# ESP32_breakout.net
KiCad netlist of a schematic drawn in Altium Designer
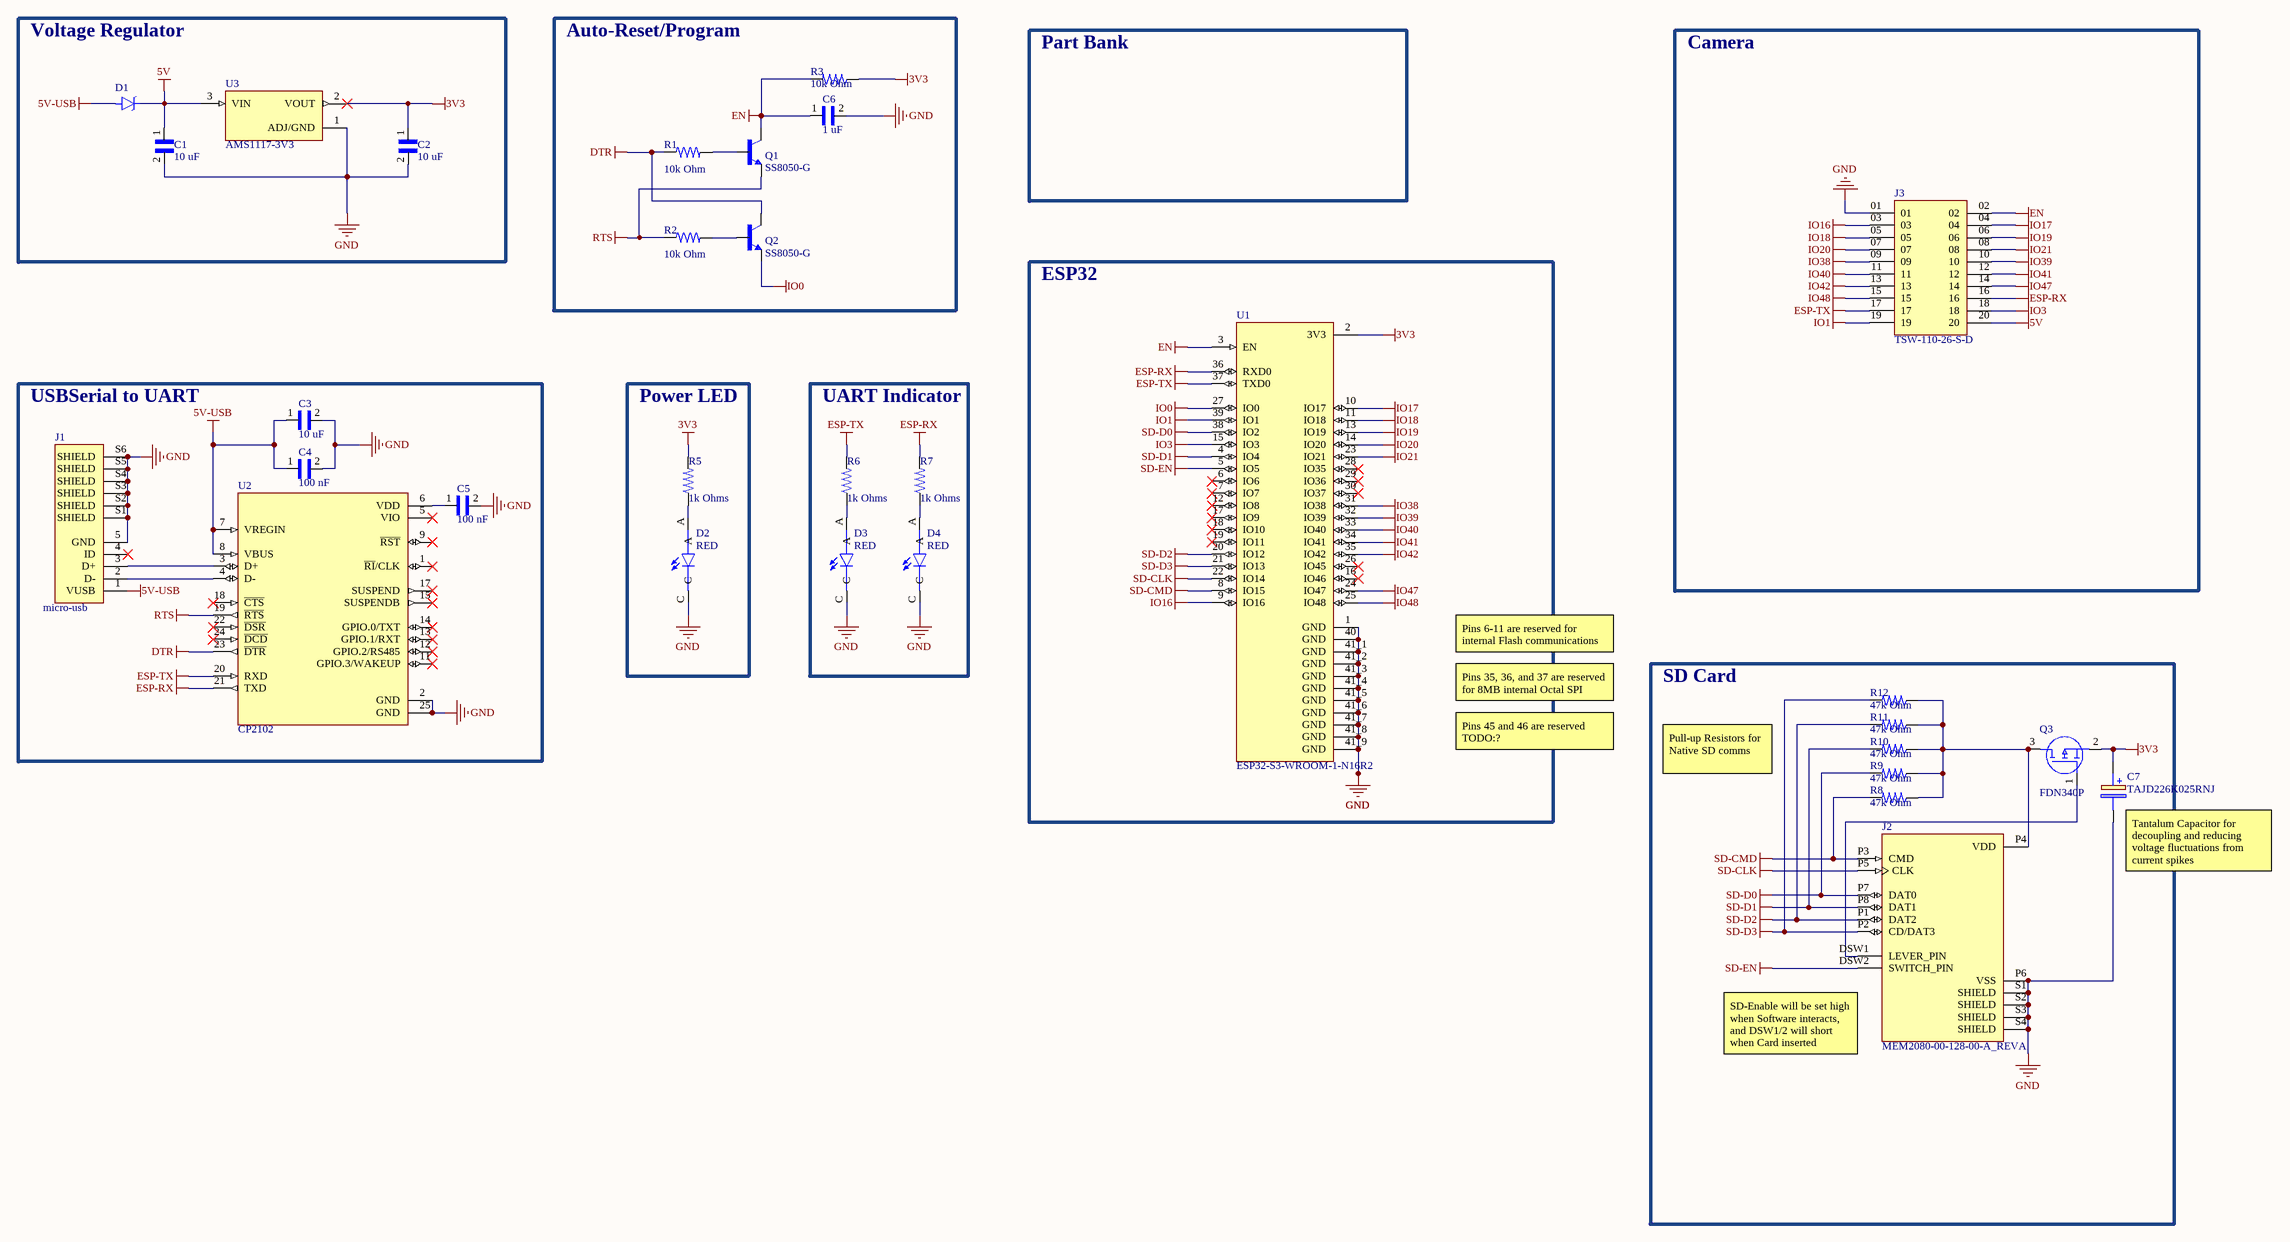
[diagram p0: ESP32_breakout.SchDoc]

(export (version "E")
  (design (tool "Eeschema 10.0.6"))
  (components
    (comp (ref "C1")
      (value "10 uF")
      (footprint "CAPC1608X90")
      (description "COMMERCIAL CHIP STD JAPAN BULK - FN TAPE/REEL, 7 INCH PAPER TAPE")
      (fields (field (name "MP") "LD03ZD475MAB2A"))
      (libsource (lib "") (part "LD03ZD475MAB2A_1"))
    )
    (comp (ref "C2")
      (value "10 uF")
      (footprint "CAPC1608X90")
      (description "COMMERCIAL CHIP STD JAPAN BULK - FN TAPE/REEL, 7 INCH PAPER TAPE")
      (fields (field (name "MP") "LD03ZD475MAB2A"))
      (libsource (lib "") (part "LD03ZD475MAB2A_1"))
    )
    (comp (ref "C3")
      (value "10 uF")
      (footprint "CAPC1608X90")
      (description "COMMERCIAL CHIP STD JAPAN BULK - FN TAPE/REEL, 7 INCH PAPER TAPE")
      (fields (field (name "MP") "LD03ZD475MAB2A"))
      (libsource (lib "Personal_Component_Lib") (part "LD03ZD475MAB2A"))
    )
    (comp (ref "C4")
      (value "100 nF")
      (footprint "CAPC1608X90")
      (description "COMMERCIAL CHIP STD JAPAN BULK - FN TAPE/REEL, 7 INCH PAPER TAPE")
      (fields (field (name "MP") "LD03ZD475MAB2A"))
      (libsource (lib "Personal_Component_Lib") (part "LD03ZD475MAB2A"))
    )
    (comp (ref "C5")
      (value "100 nF")
      (footprint "CAPC1608X90")
      (description "COMMERCIAL CHIP STD JAPAN BULK - FN TAPE/REEL, 7 INCH PAPER TAPE")
      (fields (field (name "MP") "LD03ZD475MAB2A"))
      (libsource (lib "Personal_Component_Lib") (part "LD03ZD475MAB2A"))
    )
    (comp (ref "C6")
      (value "1 uF")
      (footprint "CAPC1608X90")
      (description "COMMERCIAL CHIP STD JAPAN BULK - FN TAPE/REEL, 7 INCH PAPER TAPE")
      (fields (field (name "MP") "LD03ZD475MAB2A"))
      (libsource (lib "Personal_Component_Lib") (part "LD03ZD475MAB2A"))
    )
    (comp (ref "C7")
      (value "TAJD226K025RNJ")
      (footprint "CAPPM7344X310N")
      (fields (field (name "MOUSER PART NUMBER") "581-TAJD226K025R"))
      (libsource (lib "Personal_Component_Lib") (part "TAJD226K025RNJ"))
    )
    (comp (ref "D1")
      (value "~")
      (footprint "SOD-323")
      (description "Diode Schottky 23V 1A Surface Mount SOD-323")
      (fields (field (name "MP") "BAT20JFILM") (field (name "MF") "STMicroelectronics"))
      (libsource (lib "Personal_Component_Lib") (part "BAT20JFILM"))
    )
    (comp (ref "D2")
      (value "RED")
      (footprint "LEDC3216X110")
      (description "Orange 605nm LED Indication - Discrete 2V 1206 (3216 Metric)")
      (fields (field (name "MF") "Lite-On Inc.") (field (name "MP") "LTST-C230KFKT"))
      (libsource (lib "Personal_Component_Lib") (part "LTST-C230KFKT"))
    )
    (comp (ref "D3")
      (value "RED")
      (footprint "LEDC3216X110")
      (description "Orange 605nm LED Indication - Discrete 2V 1206 (3216 Metric)")
      (fields (field (name "MF") "Lite-On Inc.") (field (name "MP") "LTST-C230KFKT"))
      (libsource (lib "Personal_Component_Lib") (part "LTST-C230KFKT"))
    )
    (comp (ref "D4")
      (value "RED")
      (footprint "LEDC3216X110")
      (description "Orange 605nm LED Indication - Discrete 2V 1206 (3216 Metric)")
      (fields (field (name "MF") "Lite-On Inc.") (field (name "MP") "LTST-C230KFKT"))
      (libsource (lib "Personal_Component_Lib") (part "LTST-C230KFKT"))
    )
    (comp (ref "J1")
      (value "micro-usb")
      (footprint "AMPHENOL_10118193-0001LF")
      (description "Micro USB 2.0, Input Output Connectors, B TYPE RECEPTACLE")
      (fields (field (name "MP") "10118193-0001LF") (field (name "MF") "Amphenol ICC"))
      (libsource (lib "Personal_Component_Lib") (part "10118193-0001LF"))
    )
    (comp (ref "J2")
      (value "MEM2080-00-128-00-A_REVA")
      (footprint "GCT_MEM2080-00-128-00-A_REVA")
      (description "9 (8 + 1) Position Card Connector Secure Digital - microSDâ„¢ Surface Mount, Right Angle Gold")
      (fields (field (name "MP") "MEM2080-00-128-00-A") (field (name "MF") "Global Connector Technology"))
      (libsource (lib "Personal_Component_Lib") (part "MEM2080-00-128-00-A_REVA"))
    )
    (comp (ref "J3")
      (value "TSW-110-26-S-D")
      (footprint "SAMTEC_TSW-110-26-S-D")
      (libsource (lib "Personal_Component_Lib") (part "TSW-110-26-S-D"))
    )
    (comp (ref "Q1")
      (value "SS8050-G")
      (footprint "SOT95P240X111-3N")
      (description "Bipolar (BJT) Transistor NPN 25 V 1.5 A 100MHz 300 mW Surface Mount SOT-23-3")
      (fields (field (name "DIGI-KEY_PART_NUMBER") "641-1790-2-ND") (field (name "MP") "SS8050G"))
      (libsource (lib "Personal_Component_Lib") (part "SS8050-G"))
    )
    (comp (ref "Q2")
      (value "SS8050-G")
      (footprint "SOT95P240X111-3N")
      (description "Bipolar (BJT) Transistor NPN 25 V 1.5 A 100MHz 300 mW Surface Mount SOT-23-3")
      (fields (field (name "DIGI-KEY_PART_NUMBER") "641-1790-2-ND") (field (name "MP") "SS8050G"))
      (libsource (lib "Personal_Component_Lib") (part "SS8050-G"))
    )
    (comp (ref "Q3")
      (value "FDN340P")
      (footprint "SOT95P237X112-3N")
      (description "Trans MOSFET P-CH 20V 2A 3-Pin SuperSOT")
      (fields (field (name "MOUSER PART NUMBER") "512-FDN340P"))
      (libsource (lib "Personal_Component_Lib") (part "FDN340P"))
    )
    (comp (ref "R1")
      (value "10k Ohm")
      (footprint "RESC2012X65N")
      (description "RES SMD 1K OHM 0.1% 1/10W 0805")
      (fields (field (name "TOLERANCE") ".1%") (field (name "MP") "1676221-2"))
      (libsource (lib "Personal_Component_Lib") (part "1676221-2"))
    )
    (comp (ref "R2")
      (value "10k Ohm")
      (footprint "RESC2012X65N")
      (description "RES SMD 1K OHM 0.1% 1/10W 0805")
      (fields (field (name "TOLERANCE") ".1%") (field (name "MP") "1676221-2"))
      (libsource (lib "Personal_Component_Lib") (part "1676221-2"))
    )
    (comp (ref "R3")
      (value "10k Ohm")
      (footprint "RESC2012X65N")
      (description "RES SMD 1K OHM 0.1% 1/10W 0805")
      (fields (field (name "MP") "1676221-2") (field (name "MF") "TE Connectivity"))
      (libsource (lib "Personal_Component_Lib") (part "1676221-2"))
    )
    (comp (ref "R5")
      (value "1k Ohms")
      (footprint "RESC2012X65N")
      (description "RES SMD 1K OHM 0.1% 1/10W 0805")
      (fields (field (name "MP") "1676221-2") (field (name "MF") "TE Connectivity"))
      (libsource (lib "Personal_Component_Lib") (part "1676221-2"))
    )
    (comp (ref "R6")
      (value "1k Ohms")
      (footprint "RESC2012X65N")
      (description "RES SMD 1K OHM 0.1% 1/10W 0805")
      (fields (field (name "MP") "1676221-2") (field (name "MF") "TE Connectivity"))
      (libsource (lib "Personal_Component_Lib") (part "1676221-2"))
    )
    (comp (ref "R7")
      (value "1k Ohms")
      (footprint "RESC2012X65N")
      (description "RES SMD 1K OHM 0.1% 1/10W 0805")
      (fields (field (name "MP") "1676221-2") (field (name "MF") "TE Connectivity"))
      (libsource (lib "Personal_Component_Lib") (part "1676221-2"))
    )
    (comp (ref "R8")
      (value "47k Ohm")
      (footprint "RESC2012X65N")
      (description "RES SMD 1K OHM 0.1% 1/10W 0805")
      (fields (field (name "MP") "1676221-2") (field (name "MF") "TE Connectivity"))
      (libsource (lib "Personal_Component_Lib") (part "1676221-2"))
    )
    (comp (ref "R9")
      (value "47k Ohm")
      (footprint "RESC2012X65N")
      (description "RES SMD 1K OHM 0.1% 1/10W 0805")
      (fields (field (name "MP") "1676221-2") (field (name "MF") "TE Connectivity"))
      (libsource (lib "Personal_Component_Lib") (part "1676221-2"))
    )
    (comp (ref "R10")
      (value "47k Ohm")
      (footprint "RESC2012X65N")
      (description "RES SMD 1K OHM 0.1% 1/10W 0805")
      (fields (field (name "MP") "1676221-2") (field (name "MF") "TE Connectivity"))
      (libsource (lib "Personal_Component_Lib") (part "1676221-2"))
    )
    (comp (ref "R11")
      (value "47k Ohm")
      (footprint "RESC2012X65N")
      (description "RES SMD 1K OHM 0.1% 1/10W 0805")
      (fields (field (name "MP") "1676221-2") (field (name "MF") "TE Connectivity"))
      (libsource (lib "Personal_Component_Lib") (part "1676221-2"))
    )
    (comp (ref "R12")
      (value "47k Ohm")
      (footprint "RESC2012X65N")
      (description "RES SMD 1K OHM 0.1% 1/10W 0805")
      (fields (field (name "MP") "1676221-2") (field (name "MF") "TE Connectivity"))
      (libsource (lib "Personal_Component_Lib") (part "1676221-2"))
    )
    (comp (ref "U1")
      (value "ESP32-S3-WROOM-1-N16R2")
      (footprint "XCVR_ESP32-S3-WROOM-1-N16R2")
      (description "Bluetooth, WiFi 802.11b/g/n, Bluetooth v5.0 Transceiver Module 2.4GHz PCB Trace Surface Mount")
      (fields (field (name "MF") "Espressif Systems"))
      (libsource (lib "Personal_Component_Lib") (part "ESP32-S3-WROOM-1-N16R2"))
    )
    (comp (ref "U2")
      (value "CP2102")
      (footprint "QFN50P400X400X80-25N")
      (fields (field (name "MP") "CP2102N-A02-GQFN24R"))
      (libsource (lib "Personal_Component_Lib") (part "CP2102N-A02-GQFN24R"))
    )
    (comp (ref "U3")
      (value "AMS1117-3V3")
      (footprint "SOT229P700X180-4N")
      (description "Sot223/Pkg 1-Amp 3.3-Volt Low Drop Out Voltage Regulatator")
      (fields (field (name "MP") "AMS1117-3.3") (field (name "MF") "Advanced Monolithic Systems"))
      (libsource (lib "Personal_Component_Lib") (part "AMS1117-3.3"))
    )
  )
  (nets
    (net (code "1") (name "3V3") (class "Default")
      (node (ref "C2") (pin "1") (pinfunction "1_1") (pintype "passive"))
      (node (ref "C7") (pin "1") (pinfunction "+_1") (pintype "passive"))
      (node (ref "Q3") (pin "2") (pinfunction "S_2") (pintype "passive"))
      (node (ref "R3") (pin "1") (pinfunction "1_1") (pintype "passive"))
      (node (ref "R5") (pin "2") (pinfunction "2_2") (pintype "passive"))
      (node (ref "U1") (pin "2") (pinfunction "3V3_2") (pintype "power_in"))
      (node (ref "U3") (pin "2") (pinfunction "VOUT_2") (pintype "output"))
    )
    (net (code "2") (name "5V") (class "Default")
      (node (ref "C1") (pin "1") (pinfunction "1_1") (pintype "passive"))
      (node (ref "D1") (pin "C") (pinfunction "C_C") (pintype "passive"))
      (node (ref "J3") (pin "20") (pinfunction "20_20") (pintype "passive"))
      (node (ref "U3") (pin "3") (pinfunction "VIN_3") (pintype "input"))
    )
    (net (code "3") (name "5V-USB") (class "Default")
      (node (ref "C3") (pin "1") (pinfunction "1_1") (pintype "passive"))
      (node (ref "C4") (pin "1") (pinfunction "1_1") (pintype "passive"))
      (node (ref "D1") (pin "A") (pinfunction "A_A") (pintype "passive"))
      (node (ref "J1") (pin "1") (pinfunction "VUSB_1") (pintype "passive"))
      (node (ref "U2") (pin "7") (pinfunction "VREGIN_7") (pintype "input"))
      (node (ref "U2") (pin "8") (pinfunction "VBUS_8") (pintype "input"))
    )
    (net (code "4") (name "DTR") (class "Default")
      (node (ref "Q2") (pin "3") (pinfunction "C_3") (pintype "passive"))
      (node (ref "R1") (pin "1") (pinfunction "1_1") (pintype "passive"))
      (node (ref "U2") (pin "23") (pinfunction "~{DTR}_23") (pintype "output"))
    )
    (net (code "5") (name "EN") (class "Default")
      (node (ref "C6") (pin "1") (pinfunction "1_1") (pintype "passive"))
      (node (ref "J3") (pin "02") (pinfunction "02_02") (pintype "passive"))
      (node (ref "Q1") (pin "3") (pinfunction "C_3") (pintype "passive"))
      (node (ref "R3") (pin "2") (pinfunction "2_2") (pintype "passive"))
      (node (ref "U1") (pin "3") (pinfunction "EN_3") (pintype "input"))
    )
    (net (code "6") (name "ESP-RX") (class "Default")
      (node (ref "J3") (pin "16") (pinfunction "16_16") (pintype "passive"))
      (node (ref "R7") (pin "2") (pinfunction "2_2") (pintype "passive"))
      (node (ref "U1") (pin "36") (pinfunction "RXD0_36") (pintype "bidirectional"))
      (node (ref "U2") (pin "21") (pinfunction "TXD_21") (pintype "output"))
    )
    (net (code "7") (name "ESP-TX") (class "Default")
      (node (ref "J3") (pin "17") (pinfunction "17_17") (pintype "passive"))
      (node (ref "R6") (pin "2") (pinfunction "2_2") (pintype "passive"))
      (node (ref "U1") (pin "37") (pinfunction "TXD0_37") (pintype "bidirectional"))
      (node (ref "U2") (pin "20") (pinfunction "RXD_20") (pintype "input"))
    )
    (net (code "8") (name "GND") (class "Default")
      (node (ref "C1") (pin "2") (pinfunction "2_2") (pintype "passive"))
      (node (ref "C2") (pin "2") (pinfunction "2_2") (pintype "passive"))
      (node (ref "C3") (pin "2") (pinfunction "2_2") (pintype "passive"))
      (node (ref "C4") (pin "2") (pinfunction "2_2") (pintype "passive"))
      (node (ref "C5") (pin "2") (pinfunction "2_2") (pintype "passive"))
      (node (ref "C6") (pin "2") (pinfunction "2_2") (pintype "passive"))
      (node (ref "C7") (pin "2") (pinfunction "-_2") (pintype "passive"))
      (node (ref "D2") (pin "C") (pinfunction "C_C") (pintype "passive"))
      (node (ref "D3") (pin "C") (pinfunction "C_C") (pintype "passive"))
      (node (ref "D4") (pin "C") (pinfunction "C_C") (pintype "passive"))
      (node (ref "J1") (pin "5") (pinfunction "GND_5") (pintype "passive"))
      (node (ref "J1") (pin "S1") (pinfunction "SHIELD_S1") (pintype "passive"))
      (node (ref "J1") (pin "S2") (pinfunction "SHIELD_S2") (pintype "passive"))
      (node (ref "J1") (pin "S3") (pinfunction "SHIELD_S3") (pintype "passive"))
      (node (ref "J1") (pin "S4") (pinfunction "SHIELD_S4") (pintype "passive"))
      (node (ref "J1") (pin "S5") (pinfunction "SHIELD_S5") (pintype "passive"))
      (node (ref "J1") (pin "S6") (pinfunction "SHIELD_S6") (pintype "passive"))
      (node (ref "J2") (pin "P6") (pinfunction "VSS_P6") (pintype "power_in"))
      (node (ref "J2") (pin "S1") (pinfunction "SHIELD_S1") (pintype "passive"))
      (node (ref "J2") (pin "S2") (pinfunction "SHIELD_S2") (pintype "passive"))
      (node (ref "J2") (pin "S3") (pinfunction "SHIELD_S3") (pintype "passive"))
      (node (ref "J2") (pin "S4") (pinfunction "SHIELD_S4") (pintype "passive"))
      (node (ref "J3") (pin "01") (pinfunction "01_01") (pintype "passive"))
      (node (ref "U1") (pin "1") (pinfunction "GND_1") (pintype "power_in"))
      (node (ref "U1") (pin "40") (pinfunction "GND_40") (pintype "power_in"))
      (node (ref "U1") (pin "41_1") (pinfunction "GND_41_1") (pintype "power_in"))
      (node (ref "U1") (pin "41_2") (pinfunction "GND_41_2") (pintype "power_in"))
      (node (ref "U1") (pin "41_3") (pinfunction "GND_41_3") (pintype "power_in"))
      (node (ref "U1") (pin "41_4") (pinfunction "GND_41_4") (pintype "power_in"))
      (node (ref "U1") (pin "41_5") (pinfunction "GND_41_5") (pintype "power_in"))
      (node (ref "U1") (pin "41_6") (pinfunction "GND_41_6") (pintype "power_in"))
      (node (ref "U1") (pin "41_7") (pinfunction "GND_41_7") (pintype "power_in"))
      (node (ref "U1") (pin "41_8") (pinfunction "GND_41_8") (pintype "power_in"))
      (node (ref "U1") (pin "41_9") (pinfunction "GND_41_9") (pintype "power_in"))
      (node (ref "U2") (pin "2") (pinfunction "GND_2") (pintype "power_in"))
      (node (ref "U2") (pin "25") (pinfunction "GND_25") (pintype "power_in"))
      (node (ref "U3") (pin "1") (pinfunction "ADJ/GND_1") (pintype "power_in"))
    )
    (net (code "9") (name "IO0") (class "Default")
      (node (ref "Q2") (pin "2") (pinfunction "E_2") (pintype "passive"))
      (node (ref "U1") (pin "27") (pinfunction "IO0_27") (pintype "bidirectional"))
    )
    (net (code "10") (name "IO1") (class "Default")
      (node (ref "J3") (pin "19") (pinfunction "19_19") (pintype "passive"))
      (node (ref "U1") (pin "39") (pinfunction "IO1_39") (pintype "bidirectional"))
    )
    (net (code "11") (name "IO3") (class "Default")
      (node (ref "J3") (pin "18") (pinfunction "18_18") (pintype "passive"))
      (node (ref "U1") (pin "15") (pinfunction "IO3_15") (pintype "bidirectional"))
    )
    (net (code "12") (name "IO16") (class "Default")
      (node (ref "J3") (pin "03") (pinfunction "03_03") (pintype "passive"))
      (node (ref "U1") (pin "9") (pinfunction "IO16_9") (pintype "bidirectional"))
    )
    (net (code "13") (name "IO17") (class "Default")
      (node (ref "J3") (pin "04") (pinfunction "04_04") (pintype "passive"))
      (node (ref "U1") (pin "10") (pinfunction "IO17_10") (pintype "bidirectional"))
    )
    (net (code "14") (name "IO18") (class "Default")
      (node (ref "J3") (pin "05") (pinfunction "05_05") (pintype "passive"))
      (node (ref "U1") (pin "11") (pinfunction "IO18_11") (pintype "bidirectional"))
    )
    (net (code "15") (name "IO19") (class "Default")
      (node (ref "J3") (pin "06") (pinfunction "06_06") (pintype "passive"))
      (node (ref "U1") (pin "13") (pinfunction "IO19_13") (pintype "bidirectional"))
    )
    (net (code "16") (name "IO20") (class "Default")
      (node (ref "J3") (pin "07") (pinfunction "07_07") (pintype "passive"))
      (node (ref "U1") (pin "14") (pinfunction "IO20_14") (pintype "bidirectional"))
    )
    (net (code "17") (name "IO21") (class "Default")
      (node (ref "J3") (pin "08") (pinfunction "08_08") (pintype "passive"))
      (node (ref "U1") (pin "23") (pinfunction "IO21_23") (pintype "bidirectional"))
    )
    (net (code "18") (name "IO38") (class "Default")
      (node (ref "J3") (pin "09") (pinfunction "09_09") (pintype "passive"))
      (node (ref "U1") (pin "31") (pinfunction "IO38_31") (pintype "bidirectional"))
    )
    (net (code "19") (name "IO39") (class "Default")
      (node (ref "J3") (pin "10") (pinfunction "10_10") (pintype "passive"))
      (node (ref "U1") (pin "32") (pinfunction "IO39_32") (pintype "bidirectional"))
    )
    (net (code "20") (name "IO40") (class "Default")
      (node (ref "J3") (pin "11") (pinfunction "11_11") (pintype "passive"))
      (node (ref "U1") (pin "33") (pinfunction "IO40_33") (pintype "bidirectional"))
    )
    (net (code "21") (name "IO41") (class "Default")
      (node (ref "J3") (pin "12") (pinfunction "12_12") (pintype "passive"))
      (node (ref "U1") (pin "34") (pinfunction "IO41_34") (pintype "bidirectional"))
    )
    (net (code "22") (name "IO42") (class "Default")
      (node (ref "J3") (pin "13") (pinfunction "13_13") (pintype "passive"))
      (node (ref "U1") (pin "35") (pinfunction "IO42_35") (pintype "bidirectional"))
    )
    (net (code "23") (name "IO47") (class "Default")
      (node (ref "J3") (pin "14") (pinfunction "14_14") (pintype "passive"))
      (node (ref "U1") (pin "24") (pinfunction "IO47_24") (pintype "bidirectional"))
    )
    (net (code "24") (name "IO48") (class "Default")
      (node (ref "J3") (pin "15") (pinfunction "15_15") (pintype "passive"))
      (node (ref "U1") (pin "25") (pinfunction "IO48_25") (pintype "bidirectional"))
    )
    (net (code "25") (name "Net-(D2-PadA)") (class "Default")
      (node (ref "D2") (pin "A") (pinfunction "A_A") (pintype "passive"))
      (node (ref "R5") (pin "1") (pinfunction "1_1") (pintype "passive"))
    )
    (net (code "26") (name "Net-(D3-PadA)") (class "Default")
      (node (ref "D3") (pin "A") (pinfunction "A_A") (pintype "passive"))
      (node (ref "R6") (pin "1") (pinfunction "1_1") (pintype "passive"))
    )
    (net (code "27") (name "Net-(D4-PadA)") (class "Default")
      (node (ref "D4") (pin "A") (pinfunction "A_A") (pintype "passive"))
      (node (ref "R7") (pin "1") (pinfunction "1_1") (pintype "passive"))
    )
    (net (code "28") (name "Net-(J1-D+)") (class "Default")
      (node (ref "J1") (pin "3") (pinfunction "D+_3") (pintype "passive"))
      (node (ref "U2") (pin "3") (pinfunction "D+_3") (pintype "bidirectional"))
    )
    (net (code "29") (name "Net-(J1-D-)") (class "Default")
      (node (ref "J1") (pin "2") (pinfunction "D-_2") (pintype "passive"))
      (node (ref "U2") (pin "4") (pinfunction "D-_4") (pintype "bidirectional"))
    )
    (net (code "30") (name "Net-(J2-LEVER_PIN)") (class "Default")
      (node (ref "J2") (pin "DSW1") (pinfunction "LEVER_PIN_DSW1") (pintype "passive"))
      (node (ref "Q3") (pin "1") (pinfunction "G_1") (pintype "passive"))
    )
    (net (code "31") (name "Net-(J2-VDD)") (class "Default")
      (node (ref "J2") (pin "P4") (pinfunction "VDD_P4") (pintype "power_in"))
      (node (ref "Q3") (pin "3") (pinfunction "D_3") (pintype "passive"))
      (node (ref "R10") (pin "1") (pinfunction "1_1") (pintype "passive"))
      (node (ref "R11") (pin "1") (pinfunction "1_1") (pintype "passive"))
      (node (ref "R12") (pin "1") (pinfunction "1_1") (pintype "passive"))
      (node (ref "R8") (pin "1") (pinfunction "1_1") (pintype "passive"))
      (node (ref "R9") (pin "1") (pinfunction "1_1") (pintype "passive"))
    )
    (net (code "32") (name "Net-(Q1-B)") (class "Default")
      (node (ref "Q1") (pin "1") (pinfunction "B_1") (pintype "passive"))
      (node (ref "R1") (pin "2") (pinfunction "2_2") (pintype "passive"))
    )
    (net (code "33") (name "Net-(Q2-B)") (class "Default")
      (node (ref "Q2") (pin "1") (pinfunction "B_1") (pintype "passive"))
      (node (ref "R2") (pin "2") (pinfunction "2_2") (pintype "passive"))
    )
    (net (code "34") (name "Net-(U2-VDD)") (class "Default")
      (node (ref "C5") (pin "1") (pinfunction "1_1") (pintype "passive"))
      (node (ref "U2") (pin "6") (pinfunction "VDD_6") (pintype "power_in"))
    )
    (net (code "35") (name "RTS") (class "Default")
      (node (ref "Q1") (pin "2") (pinfunction "E_2") (pintype "passive"))
      (node (ref "R2") (pin "1") (pinfunction "1_1") (pintype "passive"))
      (node (ref "U2") (pin "19") (pinfunction "~{RTS}_19") (pintype "output"))
    )
    (net (code "36") (name "SD-CLK") (class "Default")
      (node (ref "J2") (pin "P5") (pinfunction "CLK_P5") (pintype "input"))
      (node (ref "U1") (pin "22") (pinfunction "IO14_22") (pintype "bidirectional"))
    )
    (net (code "37") (name "SD-CMD") (class "Default")
      (node (ref "J2") (pin "P3") (pinfunction "CMD_P3") (pintype "input"))
      (node (ref "R8") (pin "2") (pinfunction "2_2") (pintype "passive"))
      (node (ref "U1") (pin "8") (pinfunction "IO15_8") (pintype "bidirectional"))
    )
    (net (code "38") (name "SD-D0") (class "Default")
      (node (ref "J2") (pin "P7") (pinfunction "DAT0_P7") (pintype "bidirectional"))
      (node (ref "R9") (pin "2") (pinfunction "2_2") (pintype "passive"))
      (node (ref "U1") (pin "38") (pinfunction "IO2_38") (pintype "bidirectional"))
    )
    (net (code "39") (name "SD-D1") (class "Default")
      (node (ref "J2") (pin "P8") (pinfunction "DAT1_P8") (pintype "bidirectional"))
      (node (ref "R10") (pin "2") (pinfunction "2_2") (pintype "passive"))
      (node (ref "U1") (pin "4") (pinfunction "IO4_4") (pintype "bidirectional"))
    )
    (net (code "40") (name "SD-D2") (class "Default")
      (node (ref "J2") (pin "P1") (pinfunction "DAT2_P1") (pintype "bidirectional"))
      (node (ref "R11") (pin "2") (pinfunction "2_2") (pintype "passive"))
      (node (ref "U1") (pin "20") (pinfunction "IO12_20") (pintype "bidirectional"))
    )
    (net (code "41") (name "SD-D3") (class "Default")
      (node (ref "J2") (pin "P2") (pinfunction "CD/DAT3_P2") (pintype "bidirectional"))
      (node (ref "R12") (pin "2") (pinfunction "2_2") (pintype "passive"))
      (node (ref "U1") (pin "21") (pinfunction "IO13_21") (pintype "bidirectional"))
    )
    (net (code "42") (name "SD-EN") (class "Default")
      (node (ref "J2") (pin "DSW2") (pinfunction "SWITCH_PIN_DSW2") (pintype "passive"))
      (node (ref "U1") (pin "5") (pinfunction "IO5_5") (pintype "bidirectional"))
    )
    (net (code "43") (name "unconnected-(J1-ID-Pad4)") (class "Default")
      (node (ref "J1") (pin "4") (pinfunction "ID_4") (pintype "passive+no_connect"))
    )
    (net (code "44") (name "unconnected-(U1-IO6-Pad6)") (class "Default")
      (node (ref "U1") (pin "6") (pinfunction "IO6_6") (pintype "bidirectional+no_connect"))
    )
    (net (code "45") (name "unconnected-(U1-IO7-Pad7)") (class "Default")
      (node (ref "U1") (pin "7") (pinfunction "IO7_7") (pintype "bidirectional+no_connect"))
    )
    (net (code "46") (name "unconnected-(U1-IO8-Pad12)") (class "Default")
      (node (ref "U1") (pin "12") (pinfunction "IO8_12") (pintype "bidirectional+no_connect"))
    )
    (net (code "47") (name "unconnected-(U1-IO9-Pad17)") (class "Default")
      (node (ref "U1") (pin "17") (pinfunction "IO9_17") (pintype "bidirectional+no_connect"))
    )
    (net (code "48") (name "unconnected-(U1-IO10-Pad18)") (class "Default")
      (node (ref "U1") (pin "18") (pinfunction "IO10_18") (pintype "bidirectional+no_connect"))
    )
    (net (code "49") (name "unconnected-(U1-IO11-Pad19)") (class "Default")
      (node (ref "U1") (pin "19") (pinfunction "IO11_19") (pintype "bidirectional+no_connect"))
    )
    (net (code "50") (name "unconnected-(U1-IO35-Pad28)") (class "Default")
      (node (ref "U1") (pin "28") (pinfunction "IO35_28") (pintype "bidirectional+no_connect"))
    )
    (net (code "51") (name "unconnected-(U1-IO36-Pad29)") (class "Default")
      (node (ref "U1") (pin "29") (pinfunction "IO36_29") (pintype "bidirectional+no_connect"))
    )
    (net (code "52") (name "unconnected-(U1-IO37-Pad30)") (class "Default")
      (node (ref "U1") (pin "30") (pinfunction "IO37_30") (pintype "bidirectional+no_connect"))
    )
    (net (code "53") (name "unconnected-(U1-IO45-Pad26)") (class "Default")
      (node (ref "U1") (pin "26") (pinfunction "IO45_26") (pintype "bidirectional+no_connect"))
    )
    (net (code "54") (name "unconnected-(U1-IO46-Pad16)") (class "Default")
      (node (ref "U1") (pin "16") (pinfunction "IO46_16") (pintype "bidirectional+no_connect"))
    )
    (net (code "55") (name "unconnected-(U2-GPIO.0{slash}TXT-Pad14)") (class "Default")
      (node (ref "U2") (pin "14") (pinfunction "GPIO.0/TXT_14") (pintype "bidirectional+no_connect"))
    )
    (net (code "56") (name "unconnected-(U2-GPIO.1{slash}RXT-Pad13)") (class "Default")
      (node (ref "U2") (pin "13") (pinfunction "GPIO.1/RXT_13") (pintype "bidirectional+no_connect"))
    )
    (net (code "57") (name "unconnected-(U2-GPIO.2{slash}RS485-Pad12)") (class "Default")
      (node (ref "U2") (pin "12") (pinfunction "GPIO.2/RS485_12") (pintype "bidirectional+no_connect"))
    )
    (net (code "58") (name "unconnected-(U2-GPIO.3{slash}WAKEUP-Pad11)") (class "Default")
      (node (ref "U2") (pin "11") (pinfunction "GPIO.3/WAKEUP_11") (pintype "bidirectional+no_connect"))
    )
    (net (code "59") (name "unconnected-(U2-SUSPEND-Pad17)") (class "Default")
      (node (ref "U2") (pin "17") (pinfunction "SUSPEND_17") (pintype "output+no_connect"))
    )
    (net (code "60") (name "unconnected-(U2-SUSPENDB-Pad15)") (class "Default")
      (node (ref "U2") (pin "15") (pinfunction "SUSPENDB_15") (pintype "output+no_connect"))
    )
    (net (code "61") (name "unconnected-(U2-VIO-Pad5)") (class "Default")
      (node (ref "U2") (pin "5") (pinfunction "VIO_5") (pintype "power_in+no_connect"))
    )
    (net (code "62") (name "unconnected-(U2-~{CTS}-Pad18)") (class "Default")
      (node (ref "U2") (pin "18") (pinfunction "~{CTS}_18") (pintype "input+no_connect"))
    )
    (net (code "63") (name "unconnected-(U2-~{DCD}-Pad24)") (class "Default")
      (node (ref "U2") (pin "24") (pinfunction "~{DCD}_24") (pintype "input+no_connect"))
    )
    (net (code "64") (name "unconnected-(U2-~{DSR}-Pad22)") (class "Default")
      (node (ref "U2") (pin "22") (pinfunction "~{DSR}_22") (pintype "input+no_connect"))
    )
    (net (code "65") (name "unconnected-(U2-~{RI}{slash}CLK-Pad1)") (class "Default")
      (node (ref "U2") (pin "1") (pinfunction "~{RI}/CLK_1") (pintype "bidirectional+no_connect"))
    )
    (net (code "66") (name "unconnected-(U2-~{RST}-Pad9)") (class "Default")
      (node (ref "U2") (pin "9") (pinfunction "~{RST}_9") (pintype "bidirectional+no_connect"))
    )
  )
)
